# Testboard_1_3.net
KiCad netlist of a schematic drawn in EAGLE
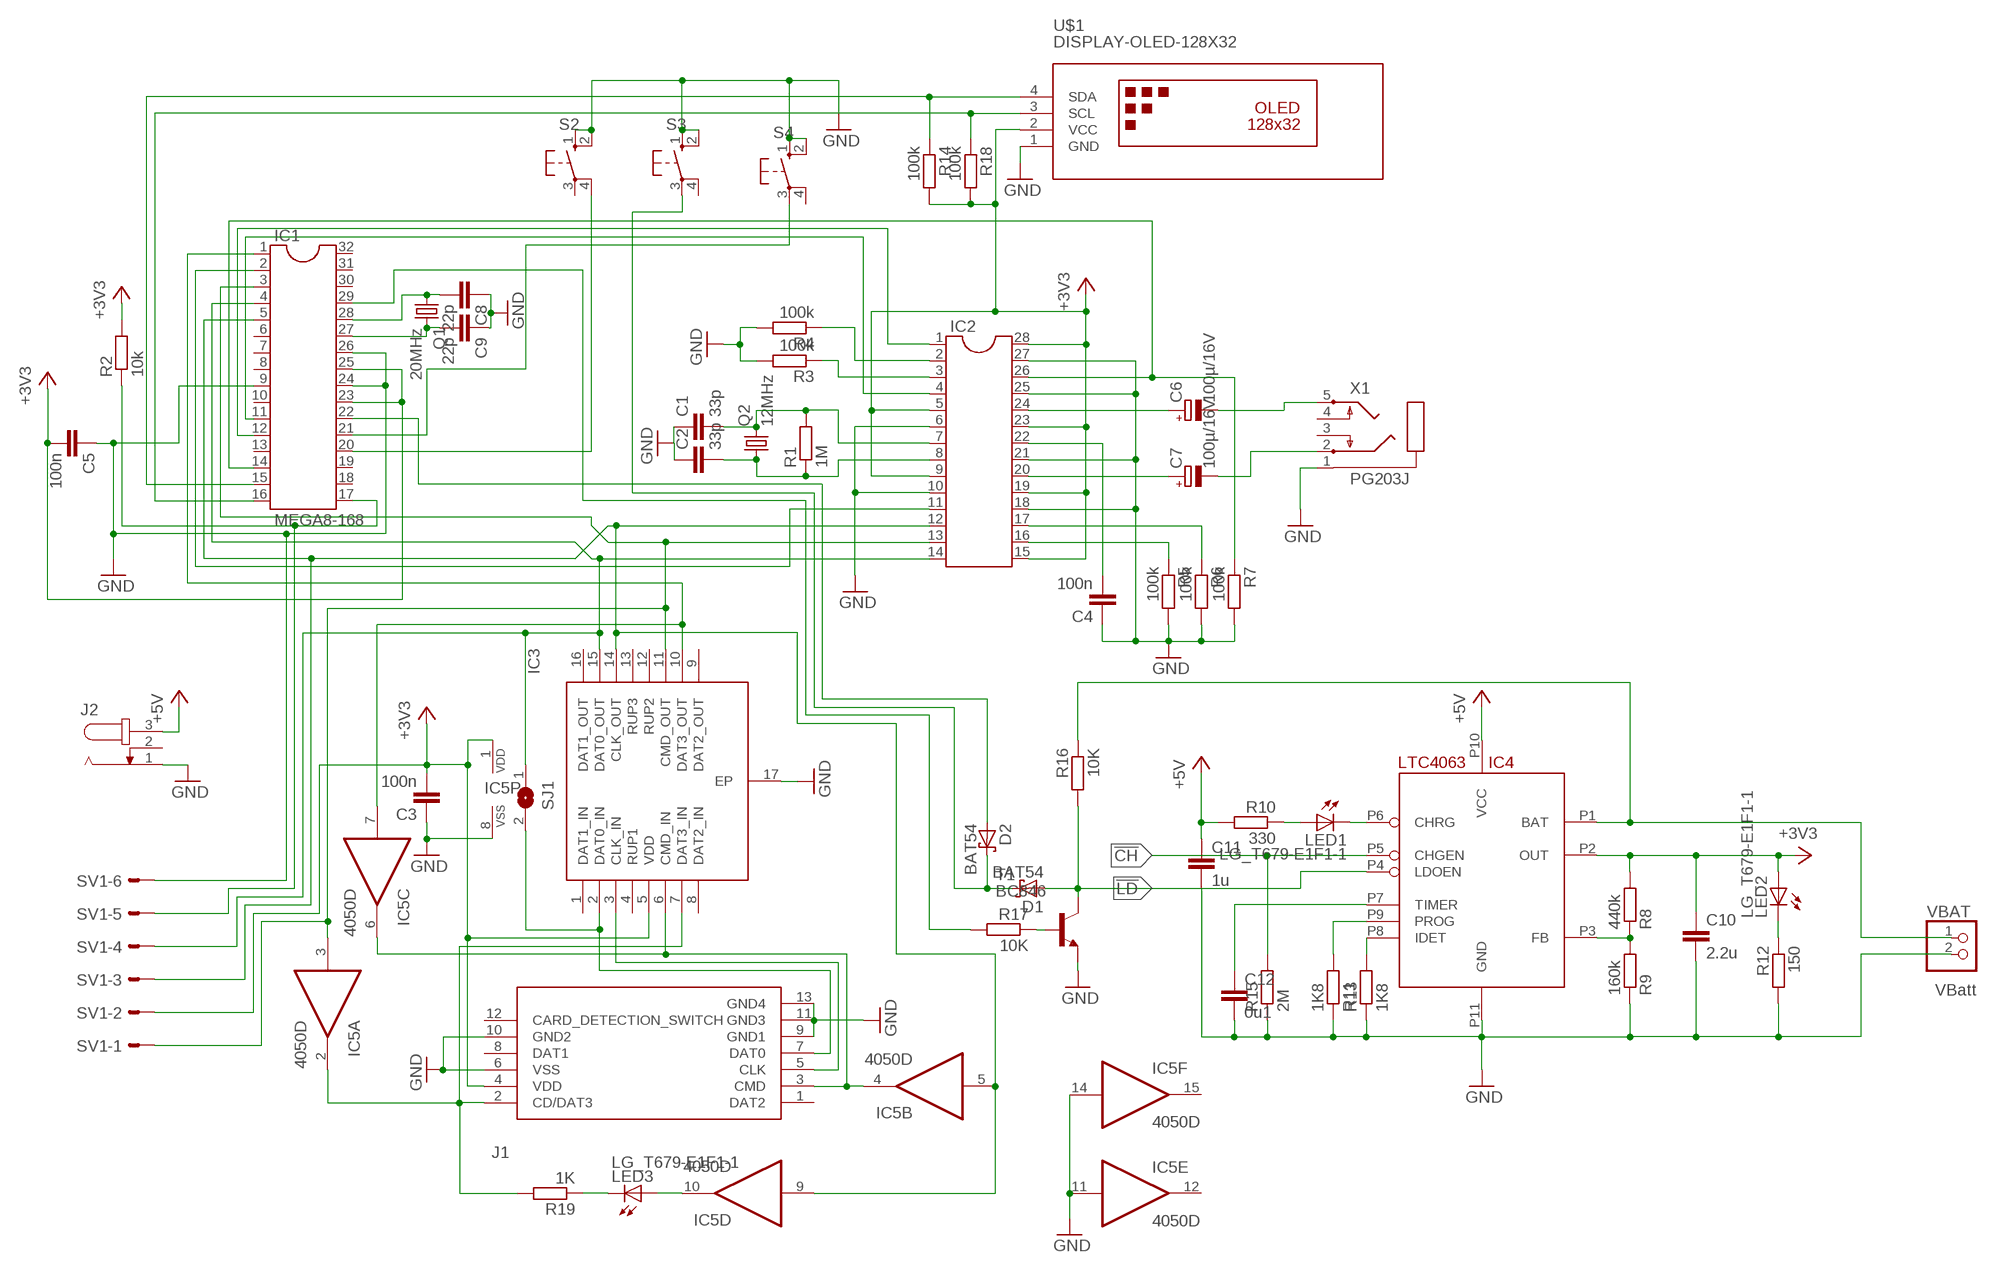
[diagram p0: schematic, sheet 1]

(export (version "E")
  (design (tool "Eeschema 10.0.6"))
  (components
    (comp (ref "C1")
      (value "33p")
      (footprint "eagle-import:C1206K")
      (libsource (lib "eagle-import") (part "C-EUC1206K"))
    )
    (comp (ref "C2")
      (value "33p")
      (footprint "eagle-import:C1206K")
      (libsource (lib "eagle-import") (part "C-EUC1206K"))
    )
    (comp (ref "C3")
      (value "100n")
      (footprint "eagle-import:C1206K")
      (libsource (lib "eagle-import") (part "C-EUC1206K"))
    )
    (comp (ref "C4")
      (value "100n")
      (footprint "eagle-import:C1206K")
      (libsource (lib "eagle-import") (part "C-EUC1206K"))
    )
    (comp (ref "C5")
      (value "100n")
      (footprint "eagle-import:C1206K")
      (libsource (lib "eagle-import") (part "C-EUC1206K"))
    )
    (comp (ref "C6")
      (value "100µ/16V")
      (footprint "eagle-import:UD-6,3X7,7_NICHICON")
      (libsource (lib "eagle-import") (part "CPOL-EUUD-6,3X7,7"))
    )
    (comp (ref "C7")
      (value "100µ/16V")
      (footprint "eagle-import:UD-6,3X7,7_NICHICON")
      (libsource (lib "eagle-import") (part "CPOL-EUUD-6,3X7,7"))
    )
    (comp (ref "C8")
      (value "22p")
      (footprint "eagle-import:C1206K")
      (libsource (lib "eagle-import") (part "rcl_334_C-EUC1206K"))
    )
    (comp (ref "C9")
      (value "22p")
      (footprint "eagle-import:C1206K")
      (libsource (lib "eagle-import") (part "rcl_334_C-EUC1206K"))
    )
    (comp (ref "C10")
      (value "2.2u")
      (footprint "eagle-import:C0805K")
      (libsource (lib "eagle-import") (part "C-EUC0805K"))
    )
    (comp (ref "C11")
      (value "1u")
      (footprint "eagle-import:C0805K")
      (libsource (lib "eagle-import") (part "C-EUC0805K"))
    )
    (comp (ref "C12")
      (value "0u1")
      (footprint "eagle-import:C0805K")
      (libsource (lib "eagle-import") (part "C-EUC0805K"))
    )
    (comp (ref "D1")
      (value "BAT54")
      (footprint "eagle-import:SOT23")
      (libsource (lib "eagle-import") (part "BAT54"))
    )
    (comp (ref "D2")
      (value "BAT54")
      (footprint "eagle-import:SOT23")
      (libsource (lib "eagle-import") (part "BAT54"))
    )
    (comp (ref "IC1")
      (value "MEGA8-168")
      (footprint "eagle-import:DIL32")
      (libsource (lib "eagle-import") (part "DIL32"))
    )
    (comp (ref "IC2")
      (value "DIL28-3")
      (footprint "eagle-import:DIL28-3")
      (libsource (lib "eagle-import") (part "DIL28-3"))
    )
    (comp (ref "IC3")
      (value "ECLAMP2410P.TCT")
      (footprint "eagle-import:SON50P160X400X65-17N")
      (fields (field (name "RS_PART_NUMBER") "6910638"))
      (libsource (lib "eagle-import") (part "ECLAMP2410P.TCT"))
    )
    (comp (ref "IC4")
      (value "LTC4063")
      (footprint "eagle-import:LTC4063")
      (libsource (lib "eagle-import") (part "LTC4063"))
    )
    (comp (ref "IC5")
      (value "4050D")
      (footprint "eagle-import:SO16")
      (libsource (lib "eagle-import") (part "4050D"))
    )
    (comp (ref "J1")
      (value "DM3CS-SF")
      (footprint "eagle-import:DM3CS-SF")
      (fields (field (name "RS_PART_NUMBER") "1664833"))
      (libsource (lib "eagle-import") (part "DM3CS-SF"))
    )
    (comp (ref "J2")
      (value "JACK-PLUG0")
      (footprint "eagle-import:SPC4077")
      (libsource (lib "eagle-import") (part "JACK-PLUG0"))
    )
    (comp (ref "LED1")
      (value "LG_T679-E1F1-1")
      (footprint "eagle-import:LED5MM")
      (libsource (lib "eagle-import") (part "LED5MM"))
    )
    (comp (ref "LED2")
      (value "LG_T679-E1F1-1")
      (footprint "eagle-import:LED5MM")
      (libsource (lib "eagle-import") (part "LED5MM"))
    )
    (comp (ref "LED3")
      (value "LG_T679-E1F1-1")
      (footprint "eagle-import:LED5MM")
      (libsource (lib "eagle-import") (part "LED5MM"))
    )
    (comp (ref "Q1")
      (value "20MHz")
      (footprint "eagle-import:HC49UP")
      (libsource (lib "eagle-import") (part "crystal_204_CRYSTALHC49UP"))
    )
    (comp (ref "Q2")
      (value "12MHz")
      (footprint "eagle-import:HC49UP")
      (libsource (lib "eagle-import") (part "CRYSTALHC49UP"))
    )
    (comp (ref "R1")
      (value "1M")
      (footprint "eagle-import:R0805")
      (libsource (lib "eagle-import") (part "rcl_334_R-EU_R0805"))
    )
    (comp (ref "R2")
      (value "10k")
      (footprint "eagle-import:0207_10")
      (libsource (lib "eagle-import") (part "rcl_334_R-EU_0207/10"))
    )
    (comp (ref "R3")
      (value "100k")
      (footprint "eagle-import:R1206")
      (libsource (lib "eagle-import") (part "rcl_334_R-EU_R1206"))
    )
    (comp (ref "R4")
      (value "100k")
      (footprint "eagle-import:R1206")
      (libsource (lib "eagle-import") (part "rcl_334_R-EU_R1206"))
    )
    (comp (ref "R5")
      (value "100k")
      (footprint "eagle-import:R0805")
      (libsource (lib "eagle-import") (part "rcl_334_R-EU_R0805"))
    )
    (comp (ref "R6")
      (value "100k")
      (footprint "eagle-import:R0805")
      (libsource (lib "eagle-import") (part "rcl_334_R-EU_R0805"))
    )
    (comp (ref "R7")
      (value "100k")
      (footprint "eagle-import:R1206")
      (libsource (lib "eagle-import") (part "rcl_334_R-EU_R1206"))
    )
    (comp (ref "R8")
      (value "440k")
      (footprint "eagle-import:R0805")
      (libsource (lib "eagle-import") (part "rcl_334_R-EU_R0805"))
    )
    (comp (ref "R9")
      (value "160k")
      (footprint "eagle-import:R0805")
      (libsource (lib "eagle-import") (part "rcl_334_R-EU_R0805"))
    )
    (comp (ref "R10")
      (value "330")
      (footprint "eagle-import:R0805")
      (libsource (lib "eagle-import") (part "rcl_334_R-EU_R0805"))
    )
    (comp (ref "R11")
      (value "1K8")
      (footprint "eagle-import:R0805")
      (libsource (lib "eagle-import") (part "R-EU_R0805"))
    )
    (comp (ref "R12")
      (value "150")
      (footprint "eagle-import:R0805")
      (libsource (lib "eagle-import") (part "rcl_334_R-EU_R0805"))
    )
    (comp (ref "R13")
      (value "1K8")
      (footprint "eagle-import:R1206")
      (libsource (lib "eagle-import") (part "rcl_334_R-EU_R1206"))
    )
    (comp (ref "R14")
      (value "100k")
      (footprint "eagle-import:R1206")
      (libsource (lib "eagle-import") (part "rcl_334_R-EU_R1206"))
    )
    (comp (ref "R15")
      (value "2M")
      (footprint "eagle-import:R0805")
      (libsource (lib "eagle-import") (part "rcl_334_R-EU_R0805"))
    )
    (comp (ref "R16")
      (value "10K")
      (footprint "eagle-import:0207_10")
      (libsource (lib "eagle-import") (part "rcl_334_R-EU_0207/10"))
    )
    (comp (ref "R17")
      (value "10K")
      (footprint "eagle-import:R0805")
      (libsource (lib "eagle-import") (part "rcl_334_R-EU_R0805"))
    )
    (comp (ref "R18")
      (value "100k")
      (footprint "eagle-import:R1206")
      (libsource (lib "eagle-import") (part "rcl_334_R-EU_R1206"))
    )
    (comp (ref "R19")
      (value "1K")
      (footprint "eagle-import:R1206")
      (libsource (lib "eagle-import") (part "rcl_334_R-EU_R1206"))
    )
    (comp (ref "S2")
      (value "10-XX")
      (footprint "eagle-import:B3F-10XX")
      (fields (field (name "MPN") "B3F-1000"))
      (libsource (lib "eagle-import") (part "10-XX"))
    )
    (comp (ref "S3")
      (value "10-XX")
      (footprint "eagle-import:B3F-10XX")
      (fields (field (name "MPN") "B3F-1000"))
      (libsource (lib "eagle-import") (part "10-XX"))
    )
    (comp (ref "S4")
      (value "10-XX")
      (footprint "eagle-import:B3F-10XX")
      (fields (field (name "MPN") "B3F-1000"))
      (libsource (lib "eagle-import") (part "10-XX"))
    )
    (comp (ref "SJ1") (value "SJ") (footprint "eagle-import:SJ") (libsource (lib "eagle-import") (part "SJ")))
    (comp (ref "SV1")
      (value "ML6E")
      (footprint "eagle-import:ML6")
      (libsource (lib "eagle-import") (part "ML6E"))
    )
    (comp (ref "T1")
      (value "BC846")
      (footprint "eagle-import:SOT23")
      (libsource (lib "eagle-import") (part "BC846"))
    )
    (comp (ref "U$1")
      (value "DISPLAY-OLED-128X32")
      (footprint "eagle-import:DISPLAY-OLED-128X32")
      (libsource (lib "eagle-import") (part "DISPLAY-OLED-128X32"))
    )
    (comp (ref "VBAT")
      (value "PINHD-1X2")
      (footprint "eagle-import:1X02")
      (libsource (lib "eagle-import") (part "PINHD-1X2"))
    )
    (comp (ref "X1")
      (value "PG203J")
      (footprint "eagle-import:PG203J")
      (libsource (lib "eagle-import") (part "PG203J"))
    )
  )
  (nets
    (net (code "1") (name "+3V3") (class "Default")
      (node (ref "C10") (pin "1") (pinfunction "1_1") (pintype "passive"))
      (node (ref "C3") (pin "2") (pinfunction "2_2") (pintype "passive"))
      (node (ref "C5") (pin "2") (pinfunction "2_2") (pintype "passive"))
      (node (ref "IC1") (pin "23") (pinfunction "23_23") (pintype "passive"))
      (node (ref "IC1") (pin "25") (pinfunction "25_25") (pintype "passive"))
      (node (ref "IC2") (pin "15") (pinfunction "15_15") (pintype "passive"))
      (node (ref "IC2") (pin "19") (pinfunction "19_19") (pintype "passive"))
      (node (ref "IC2") (pin "23") (pinfunction "23_23") (pintype "passive"))
      (node (ref "IC2") (pin "28") (pinfunction "28_28") (pintype "passive"))
      (node (ref "IC2") (pin "5") (pinfunction "5_5") (pintype "passive"))
      (node (ref "IC2") (pin "9") (pinfunction "9_9") (pintype "passive"))
      (node (ref "IC3") (pin "5") (pinfunction "VDD_5") (pintype "bidirectional"))
      (node (ref "IC4") (pin "P2") (pinfunction "OUT_P2") (pintype "output"))
      (node (ref "IC5") (pin "1") (pinfunction "VDD_1") (pintype "power_in"))
      (node (ref "J1") (pin "4") (pinfunction "VDD_4") (pintype "bidirectional"))
      (node (ref "LED2") (pin "A") (pinfunction "A_A") (pintype "passive"))
      (node (ref "R14") (pin "2") (pinfunction "2_2") (pintype "passive"))
      (node (ref "R18") (pin "2") (pinfunction "2_2") (pintype "passive"))
      (node (ref "R2") (pin "2") (pinfunction "2_2") (pintype "passive"))
      (node (ref "R8") (pin "2") (pinfunction "2_2") (pintype "passive"))
      (node (ref "SV1") (pin "2") (pinfunction "S_2") (pintype "passive"))
      (node (ref "U$1") (pin "2") (pinfunction "VCC_2") (pintype "power_in"))
    )
    (net (code "2") (name "+5V") (class "Default")
      (node (ref "C11") (pin "1") (pinfunction "1_1") (pintype "passive"))
      (node (ref "IC4") (pin "P10") (pinfunction "VCC_P10") (pintype "power_in"))
      (node (ref "J2") (pin "3") (pinfunction "3_3") (pintype "passive"))
      (node (ref "R10") (pin "2") (pinfunction "2_2") (pintype "passive"))
    )
    (net (code "3") (name "/~{CH}") (class "Default")
      (node (ref "IC4") (pin "P5") (pinfunction "CHGEN_P5") (pintype "input"))
      (node (ref "R15") (pin "2") (pinfunction "2_2") (pintype "passive"))
    )
    (net (code "4") (name "/~{LD}") (class "Default")
      (node (ref "D1") (pin "1") (pinfunction "A_1") (pintype "passive"))
      (node (ref "IC4") (pin "P4") (pinfunction "LDOEN_P4") (pintype "input"))
      (node (ref "R16") (pin "2") (pinfunction "2_2") (pintype "passive"))
      (node (ref "T1") (pin "3") (pinfunction "C_3") (pintype "passive"))
    )
    (net (code "5") (name "GND") (class "Default")
      (node (ref "C1") (pin "1") (pinfunction "1_1") (pintype "passive"))
      (node (ref "C10") (pin "2") (pinfunction "2_2") (pintype "passive"))
      (node (ref "C11") (pin "2") (pinfunction "2_2") (pintype "passive"))
      (node (ref "C12") (pin "2") (pinfunction "2_2") (pintype "passive"))
      (node (ref "C2") (pin "1") (pinfunction "1_1") (pintype "passive"))
      (node (ref "C3") (pin "1") (pinfunction "1_1") (pintype "passive"))
      (node (ref "C4") (pin "1") (pinfunction "1_1") (pintype "passive"))
      (node (ref "C5") (pin "1") (pinfunction "1_1") (pintype "passive"))
      (node (ref "C8") (pin "1") (pinfunction "1_1") (pintype "passive"))
      (node (ref "C9") (pin "1") (pinfunction "1_1") (pintype "passive"))
      (node (ref "IC1") (pin "24") (pinfunction "24_24") (pintype "passive"))
      (node (ref "IC1") (pin "26") (pinfunction "26_26") (pintype "passive"))
      (node (ref "IC1") (pin "9") (pinfunction "9_9") (pintype "passive"))
      (node (ref "IC2") (pin "10") (pinfunction "10_10") (pintype "passive"))
      (node (ref "IC2") (pin "18") (pinfunction "18_18") (pintype "passive"))
      (node (ref "IC2") (pin "21") (pinfunction "21_21") (pintype "passive"))
      (node (ref "IC2") (pin "25") (pinfunction "25_25") (pintype "passive"))
      (node (ref "IC2") (pin "27") (pinfunction "27_27") (pintype "passive"))
      (node (ref "IC2") (pin "6") (pinfunction "6_6") (pintype "passive"))
      (node (ref "IC3") (pin "17") (pinfunction "EP_17") (pintype "bidirectional"))
      (node (ref "IC4") (pin "P11") (pinfunction "GND_P11") (pintype "power_in"))
      (node (ref "IC5") (pin "11") (pinfunction "I_11") (pintype "input"))
      (node (ref "IC5") (pin "14") (pinfunction "I_14") (pintype "input"))
      (node (ref "IC5") (pin "8") (pinfunction "VSS_8") (pintype "power_in"))
      (node (ref "J1") (pin "10") (pinfunction "GND2_10") (pintype "bidirectional"))
      (node (ref "J1") (pin "11") (pinfunction "GND3_11") (pintype "bidirectional"))
      (node (ref "J1") (pin "13") (pinfunction "GND4_13") (pintype "bidirectional"))
      (node (ref "J1") (pin "6") (pinfunction "VSS_6") (pintype "bidirectional"))
      (node (ref "J1") (pin "9") (pinfunction "GND1_9") (pintype "bidirectional"))
      (node (ref "J2") (pin "1") (pinfunction "1_1") (pintype "passive"))
      (node (ref "R11") (pin "1") (pinfunction "1_1") (pintype "passive"))
      (node (ref "R12") (pin "2") (pinfunction "2_2") (pintype "passive"))
      (node (ref "R13") (pin "1") (pinfunction "1_1") (pintype "passive"))
      (node (ref "R15") (pin "1") (pinfunction "1_1") (pintype "passive"))
      (node (ref "R3") (pin "2") (pinfunction "2_2") (pintype "passive"))
      (node (ref "R4") (pin "2") (pinfunction "2_2") (pintype "passive"))
      (node (ref "R5") (pin "2") (pinfunction "2_2") (pintype "passive"))
      (node (ref "R6") (pin "2") (pinfunction "2_2") (pintype "passive"))
      (node (ref "R7") (pin "2") (pinfunction "2_2") (pintype "passive"))
      (node (ref "R9") (pin "1") (pinfunction "1_1") (pintype "passive"))
      (node (ref "S2") (pin "1") (pinfunction "S_1") (pintype "passive"))
      (node (ref "S2") (pin "2") (pinfunction "S1_2") (pintype "passive"))
      (node (ref "S3") (pin "1") (pinfunction "S_1") (pintype "passive"))
      (node (ref "S3") (pin "2") (pinfunction "S1_2") (pintype "passive"))
      (node (ref "S4") (pin "1") (pinfunction "S_1") (pintype "passive"))
      (node (ref "S4") (pin "2") (pinfunction "S1_2") (pintype "passive"))
      (node (ref "SV1") (pin "6") (pinfunction "S_6") (pintype "passive"))
      (node (ref "T1") (pin "2") (pinfunction "E_2") (pintype "passive"))
      (node (ref "U$1") (pin "1") (pinfunction "GND_1") (pintype "power_in"))
      (node (ref "VBAT") (pin "2") (pinfunction "2_2") (pintype "passive"))
      (node (ref "X1") (pin "1") (pinfunction "1_1") (pintype "passive"))
    )
    (net (code "6") (name "Net-(C1-Pad2)") (class "Default")
      (node (ref "C1") (pin "2") (pinfunction "2_2") (pintype "passive"))
      (node (ref "IC2") (pin "7") (pinfunction "7_7") (pintype "passive"))
      (node (ref "Q2") (pin "2") (pinfunction "2_2") (pintype "passive"))
      (node (ref "R1") (pin "2") (pinfunction "2_2") (pintype "passive"))
    )
    (net (code "7") (name "Net-(C2-Pad2)") (class "Default")
      (node (ref "C2") (pin "2") (pinfunction "2_2") (pintype "passive"))
      (node (ref "IC2") (pin "8") (pinfunction "8_8") (pintype "passive"))
      (node (ref "Q2") (pin "1") (pinfunction "1_1") (pintype "passive"))
      (node (ref "R1") (pin "1") (pinfunction "1_1") (pintype "passive"))
    )
    (net (code "8") (name "Net-(C4-Pad2)") (class "Default")
      (node (ref "C4") (pin "2") (pinfunction "2_2") (pintype "passive"))
      (node (ref "IC2") (pin "22") (pinfunction "22_22") (pintype "passive"))
    )
    (net (code "9") (name "Net-(C6-Pad+)") (class "Default")
      (node (ref "C6") (pin "+") (pinfunction "+_+") (pintype "passive"))
      (node (ref "IC2") (pin "24") (pinfunction "24_24") (pintype "passive"))
    )
    (net (code "10") (name "Net-(C6-Pad-)") (class "Default")
      (node (ref "C6") (pin "-") (pinfunction "-_-") (pintype "passive"))
      (node (ref "X1") (pin "5") (pinfunction "5_5") (pintype "passive"))
    )
    (net (code "11") (name "Net-(C7-Pad+)") (class "Default")
      (node (ref "C7") (pin "+") (pinfunction "+_+") (pintype "passive"))
      (node (ref "IC2") (pin "20") (pinfunction "20_20") (pintype "passive"))
    )
    (net (code "12") (name "Net-(C7-Pad-)") (class "Default")
      (node (ref "C7") (pin "-") (pinfunction "-_-") (pintype "passive"))
      (node (ref "X1") (pin "2") (pinfunction "2_2") (pintype "passive"))
    )
    (net (code "13") (name "Net-(C8-Pad2)") (class "Default")
      (node (ref "C8") (pin "2") (pinfunction "2_2") (pintype "passive"))
      (node (ref "IC1") (pin "28") (pinfunction "28_28") (pintype "passive"))
      (node (ref "Q1") (pin "1") (pinfunction "1_1") (pintype "passive"))
    )
    (net (code "14") (name "Net-(C9-Pad2)") (class "Default")
      (node (ref "C9") (pin "2") (pinfunction "2_2") (pintype "passive"))
      (node (ref "IC1") (pin "27") (pinfunction "27_27") (pintype "passive"))
      (node (ref "Q1") (pin "2") (pinfunction "2_2") (pintype "passive"))
    )
    (net (code "15") (name "Net-(D1-C)") (class "Default")
      (node (ref "D1") (pin "3") (pinfunction "C_3") (pintype "passive"))
      (node (ref "D2") (pin "3") (pinfunction "C_3") (pintype "passive"))
      (node (ref "S3") (pin "3") (pinfunction "P_3") (pintype "passive"))
    )
    (net (code "16") (name "Net-(D2-A)") (class "Default")
      (node (ref "D2") (pin "1") (pinfunction "A_1") (pintype "passive"))
      (node (ref "IC1") (pin "22") (pinfunction "22_22") (pintype "passive"))
    )
    (net (code "17") (name "Net-(IC1-Pad2)") (class "Default")
      (node (ref "IC1") (pin "2") (pinfunction "2_2") (pintype "passive"))
      (node (ref "IC2") (pin "11") (pinfunction "11_11") (pintype "passive"))
    )
    (net (code "18") (name "Net-(IC1-Pad11)") (class "Default")
      (node (ref "IC1") (pin "11") (pinfunction "11_11") (pintype "passive"))
      (node (ref "IC2") (pin "4") (pinfunction "4_4") (pintype "passive"))
    )
    (net (code "19") (name "Net-(IC1-Pad12)") (class "Default")
      (node (ref "IC1") (pin "12") (pinfunction "12_12") (pintype "passive"))
      (node (ref "IC2") (pin "1") (pinfunction "1_1") (pintype "passive"))
    )
    (net (code "20") (name "Net-(IC1-Pad14)") (class "Default")
      (node (ref "IC1") (pin "14") (pinfunction "14_14") (pintype "passive"))
      (node (ref "IC2") (pin "26") (pinfunction "26_26") (pintype "passive"))
      (node (ref "R7") (pin "1") (pinfunction "1_1") (pintype "passive"))
    )
    (net (code "21") (name "Net-(IC1-Pad29)") (class "Default")
      (node (ref "IC1") (pin "29") (pinfunction "29_29") (pintype "passive"))
      (node (ref "R17") (pin "2") (pinfunction "2_2") (pintype "passive"))
    )
    (net (code "22") (name "Net-(IC2-Pad2)") (class "Default")
      (node (ref "IC2") (pin "2") (pinfunction "2_2") (pintype "passive"))
      (node (ref "R4") (pin "1") (pinfunction "1_1") (pintype "passive"))
    )
    (net (code "23") (name "Net-(IC2-Pad3)") (class "Default")
      (node (ref "IC2") (pin "3") (pinfunction "3_3") (pintype "passive"))
      (node (ref "R3") (pin "1") (pinfunction "1_1") (pintype "passive"))
    )
    (net (code "24") (name "Net-(IC2-Pad16)") (class "Default")
      (node (ref "IC2") (pin "16") (pinfunction "16_16") (pintype "passive"))
      (node (ref "R5") (pin "1") (pinfunction "1_1") (pintype "passive"))
    )
    (net (code "25") (name "Net-(IC2-Pad17)") (class "Default")
      (node (ref "IC2") (pin "17") (pinfunction "17_17") (pintype "passive"))
      (node (ref "R6") (pin "1") (pinfunction "1_1") (pintype "passive"))
    )
    (net (code "26") (name "Net-(IC3-CLK_IN)") (class "Default")
      (node (ref "IC3") (pin "3") (pinfunction "CLK_IN_3") (pintype "bidirectional"))
      (node (ref "J1") (pin "5") (pinfunction "CLK_5") (pintype "bidirectional"))
    )
    (net (code "27") (name "Net-(IC3-CLK_OUT)") (class "Default")
      (node (ref "IC1") (pin "5") (pinfunction "5_5") (pintype "passive"))
      (node (ref "IC2") (pin "12") (pinfunction "12_12") (pintype "passive"))
      (node (ref "IC3") (pin "14") (pinfunction "CLK_OUT_14") (pintype "bidirectional"))
      (node (ref "IC5") (pin "5") (pinfunction "I_5") (pintype "input"))
      (node (ref "IC5") (pin "9") (pinfunction "I_9") (pintype "input"))
      (node (ref "SV1") (pin "3") (pinfunction "S_3") (pintype "passive"))
    )
    (net (code "28") (name "Net-(IC3-CMD_IN)") (class "Default")
      (node (ref "IC3") (pin "6") (pinfunction "CMD_IN_6") (pintype "bidirectional"))
      (node (ref "IC5") (pin "4") (pinfunction "O_4") (pintype "output"))
      (node (ref "IC5") (pin "6") (pinfunction "O_6") (pintype "output"))
      (node (ref "J1") (pin "3") (pinfunction "CMD_3") (pintype "bidirectional"))
    )
    (net (code "29") (name "Net-(IC3-CMD_OUT)") (class "Default")
      (node (ref "IC1") (pin "3") (pinfunction "3_3") (pintype "passive"))
      (node (ref "IC2") (pin "13") (pinfunction "13_13") (pintype "passive"))
      (node (ref "IC3") (pin "11") (pinfunction "CMD_OUT_11") (pintype "bidirectional"))
      (node (ref "IC5") (pin "3") (pinfunction "I_3") (pintype "input"))
      (node (ref "SV1") (pin "1") (pinfunction "S_1") (pintype "passive"))
    )
    (net (code "30") (name "Net-(IC3-DAT0_IN)") (class "Default")
      (node (ref "IC3") (pin "2") (pinfunction "DAT0_IN_2") (pintype "bidirectional"))
      (node (ref "J1") (pin "7") (pinfunction "DAT0_7") (pintype "bidirectional"))
      (node (ref "SJ1") (pin "2") (pinfunction "2_2") (pintype "passive"))
    )
    (net (code "31") (name "Net-(IC3-DAT0_OUT)") (class "Default")
      (node (ref "IC1") (pin "4") (pinfunction "4_4") (pintype "passive"))
      (node (ref "IC2") (pin "14") (pinfunction "14_14") (pintype "passive"))
      (node (ref "IC3") (pin "15") (pinfunction "DAT0_OUT_15") (pintype "bidirectional"))
      (node (ref "SJ1") (pin "1") (pinfunction "1_1") (pintype "passive"))
      (node (ref "SV1") (pin "4") (pinfunction "S_4") (pintype "passive"))
    )
    (net (code "32") (name "Net-(IC3-DAT3_IN)") (class "Default")
      (node (ref "IC3") (pin "7") (pinfunction "DAT3_IN_7") (pintype "bidirectional"))
      (node (ref "IC5") (pin "2") (pinfunction "O_2") (pintype "output"))
      (node (ref "J1") (pin "2") (pinfunction "CD/DAT3_2") (pintype "bidirectional"))
      (node (ref "R19") (pin "2") (pinfunction "2_2") (pintype "passive"))
    )
    (net (code "33") (name "Net-(IC3-DAT3_OUT)") (class "Default")
      (node (ref "IC1") (pin "1") (pinfunction "1_1") (pintype "passive"))
      (node (ref "IC3") (pin "10") (pinfunction "DAT3_OUT_10") (pintype "bidirectional"))
      (node (ref "IC5") (pin "7") (pinfunction "I_7") (pintype "input"))
    )
    (net (code "34") (name "Net-(IC4-BAT)") (class "Default")
      (node (ref "IC4") (pin "P1") (pinfunction "BAT_P1") (pintype "output"))
      (node (ref "R16") (pin "1") (pinfunction "1_1") (pintype "passive"))
      (node (ref "VBAT") (pin "1") (pinfunction "1_1") (pintype "passive"))
    )
    (net (code "35") (name "Net-(IC4-CHRG)") (class "Default")
      (node (ref "IC4") (pin "P6") (pinfunction "CHRG_P6") (pintype "output"))
      (node (ref "LED1") (pin "K") (pinfunction "C_K") (pintype "passive"))
    )
    (net (code "36") (name "Net-(IC4-FB)") (class "Default")
      (node (ref "IC4") (pin "P3") (pinfunction "FB_P3") (pintype "passive"))
      (node (ref "R8") (pin "1") (pinfunction "1_1") (pintype "passive"))
      (node (ref "R9") (pin "2") (pinfunction "2_2") (pintype "passive"))
    )
    (net (code "37") (name "Net-(IC4-IDET)") (class "Default")
      (node (ref "IC4") (pin "P8") (pinfunction "IDET_P8") (pintype "passive"))
      (node (ref "R13") (pin "2") (pinfunction "2_2") (pintype "passive"))
    )
    (net (code "38") (name "Net-(IC4-PROG)") (class "Default")
      (node (ref "IC4") (pin "P9") (pinfunction "PROG_P9") (pintype "passive"))
      (node (ref "R11") (pin "2") (pinfunction "2_2") (pintype "passive"))
    )
    (net (code "39") (name "Net-(IC4-TIMER)") (class "Default")
      (node (ref "C12") (pin "1") (pinfunction "1_1") (pintype "passive"))
      (node (ref "IC4") (pin "P7") (pinfunction "TIMER_P7") (pintype "passive"))
    )
    (net (code "40") (name "Net-(IC5D-O)") (class "Default")
      (node (ref "IC5") (pin "10") (pinfunction "O_10") (pintype "output"))
      (node (ref "LED3") (pin "A") (pinfunction "A_A") (pintype "passive"))
    )
    (net (code "41") (name "Net-(LED1-PadA)") (class "Default")
      (node (ref "LED1") (pin "A") (pinfunction "A_A") (pintype "passive"))
      (node (ref "R10") (pin "1") (pinfunction "1_1") (pintype "passive"))
    )
    (net (code "42") (name "Net-(LED2-C)") (class "Default")
      (node (ref "LED2") (pin "K") (pinfunction "C_K") (pintype "passive"))
      (node (ref "R12") (pin "1") (pinfunction "1_1") (pintype "passive"))
    )
    (net (code "43") (name "Net-(LED3-C)") (class "Default")
      (node (ref "LED3") (pin "K") (pinfunction "C_K") (pintype "passive"))
      (node (ref "R19") (pin "1") (pinfunction "1_1") (pintype "passive"))
    )
    (net (code "44") (name "Net-(S2-P1)") (class "Default")
      (node (ref "IC1") (pin "20") (pinfunction "20_20") (pintype "passive"))
      (node (ref "S2") (pin "4") (pinfunction "P1_4") (pintype "passive"))
    )
    (net (code "45") (name "Net-(S4-P)") (class "Default")
      (node (ref "IC1") (pin "21") (pinfunction "21_21") (pintype "passive"))
      (node (ref "S4") (pin "3") (pinfunction "P_3") (pintype "passive"))
    )
    (net (code "46") (name "Net-(SV1E-S)") (class "Default")
      (node (ref "IC1") (pin "17") (pinfunction "17_17") (pintype "passive"))
      (node (ref "R2") (pin "1") (pinfunction "1_1") (pintype "passive"))
      (node (ref "SV1") (pin "5") (pinfunction "S_5") (pintype "passive"))
    )
    (net (code "47") (name "Net-(T1-B)") (class "Default")
      (node (ref "R17") (pin "1") (pinfunction "1_1") (pintype "passive"))
      (node (ref "T1") (pin "1") (pinfunction "B_1") (pintype "passive"))
    )
    (net (code "48") (name "Net-(U$1-SCL)") (class "Default")
      (node (ref "IC1") (pin "16") (pinfunction "16_16") (pintype "passive"))
      (node (ref "R18") (pin "1") (pinfunction "1_1") (pintype "passive"))
      (node (ref "U$1") (pin "3") (pinfunction "SCL_3") (pintype "bidirectional"))
    )
    (net (code "49") (name "Net-(U$1-SDA)") (class "Default")
      (node (ref "IC1") (pin "15") (pinfunction "15_15") (pintype "passive"))
      (node (ref "R14") (pin "1") (pinfunction "1_1") (pintype "passive"))
      (node (ref "U$1") (pin "4") (pinfunction "SDA_4") (pintype "bidirectional"))
    )
    (net (code "50") (name "unconnected-(IC1-Pad6)") (class "Default")
      (node (ref "IC1") (pin "6") (pinfunction "6_6") (pintype "passive"))
    )
    (net (code "51") (name "unconnected-(IC1-Pad7)") (class "Default")
      (node (ref "IC1") (pin "7") (pinfunction "7_7") (pintype "passive"))
    )
    (net (code "52") (name "unconnected-(IC1-Pad8)") (class "Default")
      (node (ref "IC1") (pin "8") (pinfunction "8_8") (pintype "passive"))
    )
    (net (code "53") (name "unconnected-(IC1-Pad10)") (class "Default")
      (node (ref "IC1") (pin "10") (pinfunction "10_10") (pintype "passive"))
    )
    (net (code "54") (name "unconnected-(IC1-Pad13)") (class "Default")
      (node (ref "IC1") (pin "13") (pinfunction "13_13") (pintype "passive"))
    )
    (net (code "55") (name "unconnected-(IC1-Pad18)") (class "Default")
      (node (ref "IC1") (pin "18") (pinfunction "18_18") (pintype "passive"))
    )
    (net (code "56") (name "unconnected-(IC1-Pad19)") (class "Default")
      (node (ref "IC1") (pin "19") (pinfunction "19_19") (pintype "passive"))
    )
    (net (code "57") (name "unconnected-(IC1-Pad30)") (class "Default")
      (node (ref "IC1") (pin "30") (pinfunction "30_30") (pintype "passive"))
    )
    (net (code "58") (name "unconnected-(IC1-Pad31)") (class "Default")
      (node (ref "IC1") (pin "31") (pinfunction "31_31") (pintype "passive"))
    )
    (net (code "59") (name "unconnected-(IC1-Pad32)") (class "Default")
      (node (ref "IC1") (pin "32") (pinfunction "32_32") (pintype "passive"))
    )
    (net (code "60") (name "unconnected-(IC3-DAT1_IN-Pad1)") (class "Default")
      (node (ref "IC3") (pin "1") (pinfunction "DAT1_IN_1") (pintype "bidirectional"))
    )
    (net (code "61") (name "unconnected-(IC3-DAT1_OUT-Pad16)") (class "Default")
      (node (ref "IC3") (pin "16") (pinfunction "DAT1_OUT_16") (pintype "bidirectional"))
    )
    (net (code "62") (name "unconnected-(IC3-DAT2_IN-Pad8)") (class "Default")
      (node (ref "IC3") (pin "8") (pinfunction "DAT2_IN_8") (pintype "bidirectional"))
    )
    (net (code "63") (name "unconnected-(IC3-DAT2_OUT-Pad9)") (class "Default")
      (node (ref "IC3") (pin "9") (pinfunction "DAT2_OUT_9") (pintype "bidirectional"))
    )
    (net (code "64") (name "unconnected-(IC3-RUP1-Pad4)") (class "Default")
      (node (ref "IC3") (pin "4") (pinfunction "RUP1_4") (pintype "bidirectional"))
    )
    (net (code "65") (name "unconnected-(IC3-RUP2-Pad12)") (class "Default")
      (node (ref "IC3") (pin "12") (pinfunction "RUP2_12") (pintype "bidirectional"))
    )
    (net (code "66") (name "unconnected-(IC3-RUP3-Pad13)") (class "Default")
      (node (ref "IC3") (pin "13") (pinfunction "RUP3_13") (pintype "bidirectional"))
    )
    (net (code "67") (name "unconnected-(IC5E-O-Pad12)") (class "Default")
      (node (ref "IC5") (pin "12") (pinfunction "O_12") (pintype "output"))
    )
    (net (code "68") (name "unconnected-(IC5F-O-Pad15)") (class "Default")
      (node (ref "IC5") (pin "15") (pinfunction "O_15") (pintype "output"))
    )
    (net (code "69") (name "unconnected-(J1-CARD_DETECTION_SWITCH-Pad12)") (class "Default")
      (node (ref "J1") (pin "12") (pinfunction "CARD_DETECTION_SWITCH_12") (pintype "bidirectional"))
    )
    (net (code "70") (name "unconnected-(J1-DAT1-Pad8)") (class "Default")
      (node (ref "J1") (pin "8") (pinfunction "DAT1_8") (pintype "bidirectional"))
    )
    (net (code "71") (name "unconnected-(J1-DAT2-Pad1)") (class "Default")
      (node (ref "J1") (pin "1") (pinfunction "DAT2_1") (pintype "bidirectional"))
    )
    (net (code "72") (name "unconnected-(J2-Pad2)") (class "Default")
      (node (ref "J2") (pin "2") (pinfunction "2_2") (pintype "passive"))
    )
    (net (code "73") (name "unconnected-(S2-P-Pad3)") (class "Default")
      (node (ref "S2") (pin "3") (pinfunction "P_3") (pintype "passive"))
    )
    (net (code "74") (name "unconnected-(S3-P1-Pad4)") (class "Default")
      (node (ref "S3") (pin "4") (pinfunction "P1_4") (pintype "passive"))
    )
    (net (code "75") (name "unconnected-(S4-P1-Pad4)") (class "Default")
      (node (ref "S4") (pin "4") (pinfunction "P1_4") (pintype "passive"))
    )
    (net (code "76") (name "unconnected-(X1-Pad3)") (class "Default")
      (node (ref "X1") (pin "3") (pinfunction "3_3") (pintype "passive"))
    )
    (net (code "77") (name "unconnected-(X1-Pad4)") (class "Default")
      (node (ref "X1") (pin "4") (pinfunction "4_4") (pintype "passive"))
    )
  )
)
